# AudioInputs_16.net
KiCad netlist of a schematic drawn in Altium Designer
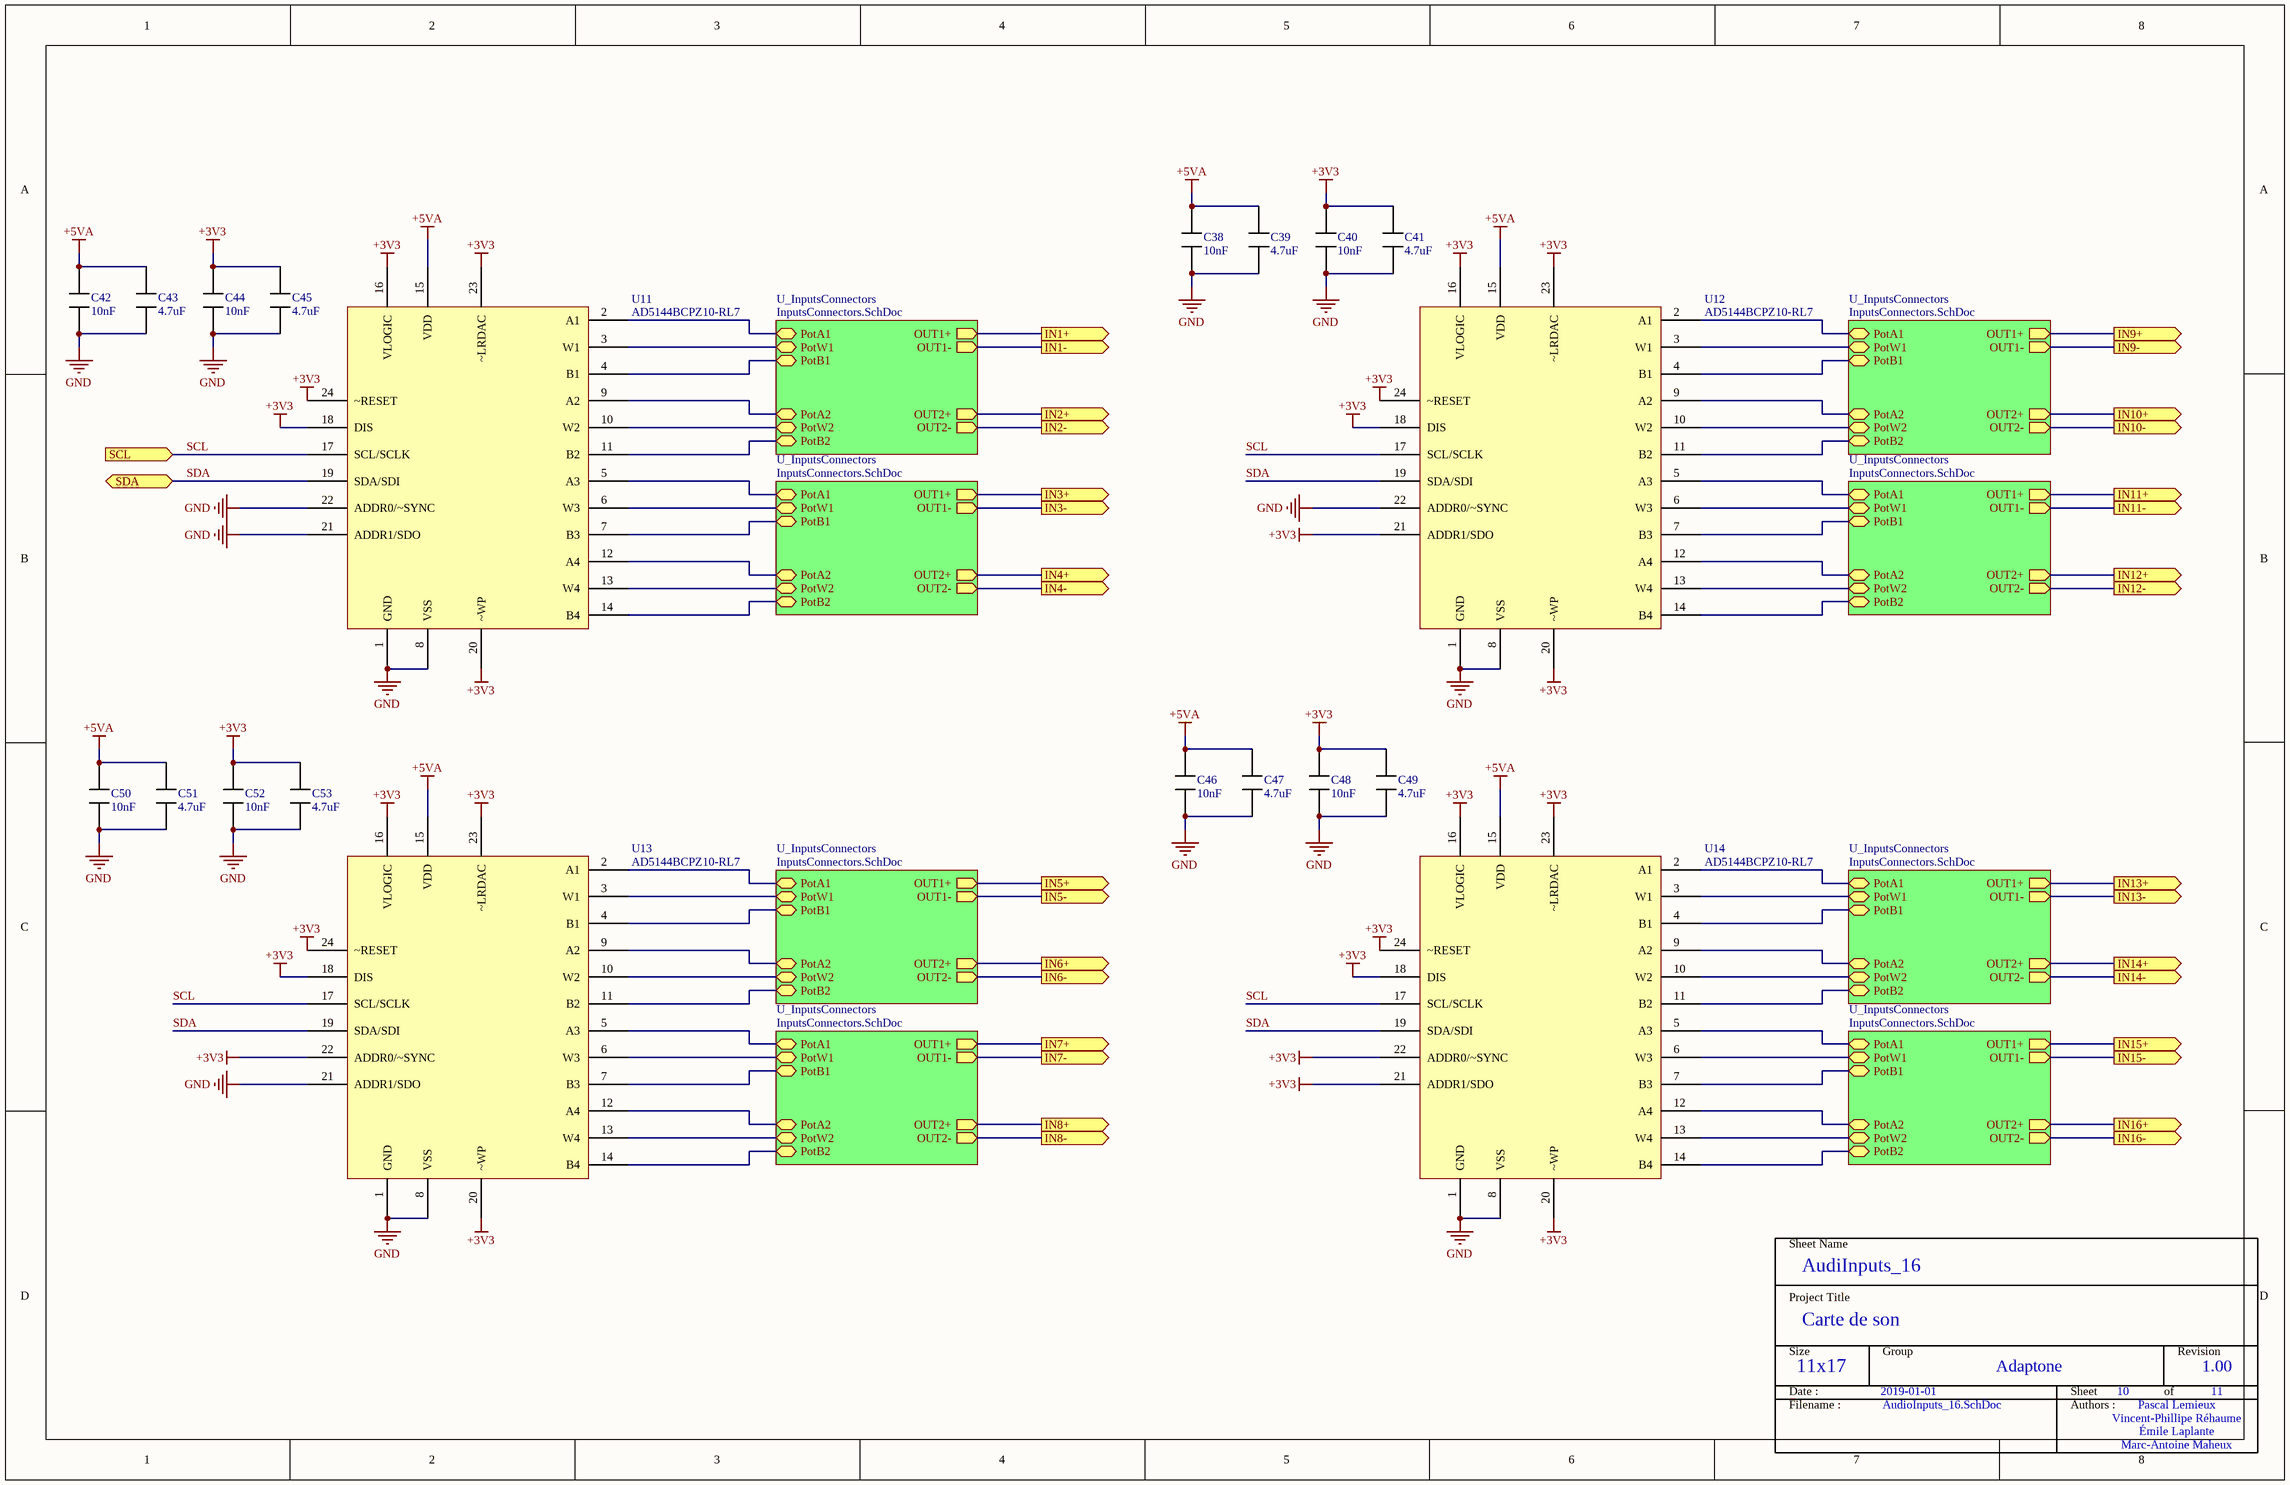
[diagram p0: AudioInputs_16.SchDoc]

(export (version "E")
  (design (tool "Eeschema 10.0.6"))
  (components
    (comp (ref "C38")
      (value "10nF")
      (footprint "0402")
      (description "Capacitor")
      (fields (field (name "MFG") "Samsung"))
      (libsource (lib "LIB_ADAPTONE_PASCAL_LEMIEUX") (part "Capacitor"))
    )
    (comp (ref "C39")
      (value "4.7uF")
      (footprint "0402")
      (description "Capacitor")
      (fields (field (name "MFG") "Samsung"))
      (libsource (lib "LIB_ADAPTONE_PASCAL_LEMIEUX") (part "Capacitor"))
    )
    (comp (ref "C40")
      (value "10nF")
      (footprint "0402")
      (description "Capacitor")
      (fields (field (name "MFG") "Samsung"))
      (libsource (lib "LIB_ADAPTONE_PASCAL_LEMIEUX") (part "Capacitor"))
    )
    (comp (ref "C41")
      (value "4.7uF")
      (footprint "0402")
      (description "Capacitor")
      (fields (field (name "MFG") "Samsung"))
      (libsource (lib "LIB_ADAPTONE_PASCAL_LEMIEUX") (part "Capacitor"))
    )
    (comp (ref "C42")
      (value "10nF")
      (footprint "0402")
      (description "Capacitor")
      (fields (field (name "MFG") "Samsung"))
      (libsource (lib "LIB_ADAPTONE_PASCAL_LEMIEUX") (part "Capacitor"))
    )
    (comp (ref "C43")
      (value "4.7uF")
      (footprint "0402")
      (description "Capacitor")
      (fields (field (name "MFG") "Samsung"))
      (libsource (lib "LIB_ADAPTONE_PASCAL_LEMIEUX") (part "Capacitor"))
    )
    (comp (ref "C44")
      (value "10nF")
      (footprint "0402")
      (description "Capacitor")
      (fields (field (name "MFG") "Samsung"))
      (libsource (lib "LIB_ADAPTONE_PASCAL_LEMIEUX") (part "Capacitor"))
    )
    (comp (ref "C45")
      (value "4.7uF")
      (footprint "0402")
      (description "Capacitor")
      (fields (field (name "MFG") "Samsung"))
      (libsource (lib "LIB_ADAPTONE_PASCAL_LEMIEUX") (part "Capacitor"))
    )
    (comp (ref "C46")
      (value "10nF")
      (footprint "0402")
      (description "Capacitor")
      (fields (field (name "MFG") "Samsung"))
      (libsource (lib "LIB_ADAPTONE_PASCAL_LEMIEUX") (part "Capacitor"))
    )
    (comp (ref "C47")
      (value "4.7uF")
      (footprint "0402")
      (description "Capacitor")
      (fields (field (name "MFG") "Samsung"))
      (libsource (lib "LIB_ADAPTONE_PASCAL_LEMIEUX") (part "Capacitor"))
    )
    (comp (ref "C48")
      (value "10nF")
      (footprint "0402")
      (description "Capacitor")
      (fields (field (name "MFG") "Samsung"))
      (libsource (lib "LIB_ADAPTONE_PASCAL_LEMIEUX") (part "Capacitor"))
    )
    (comp (ref "C49")
      (value "4.7uF")
      (footprint "0402")
      (description "Capacitor")
      (fields (field (name "MFG") "Samsung"))
      (libsource (lib "LIB_ADAPTONE_PASCAL_LEMIEUX") (part "Capacitor"))
    )
    (comp (ref "C50")
      (value "10nF")
      (footprint "0402")
      (description "Capacitor")
      (fields (field (name "MFG") "Samsung"))
      (libsource (lib "LIB_ADAPTONE_PASCAL_LEMIEUX") (part "Capacitor"))
    )
    (comp (ref "C51")
      (value "4.7uF")
      (footprint "0402")
      (description "Capacitor")
      (fields (field (name "MFG") "Samsung"))
      (libsource (lib "LIB_ADAPTONE_PASCAL_LEMIEUX") (part "Capacitor"))
    )
    (comp (ref "C52")
      (value "10nF")
      (footprint "0402")
      (description "Capacitor")
      (fields (field (name "MFG") "Samsung"))
      (libsource (lib "LIB_ADAPTONE_PASCAL_LEMIEUX") (part "Capacitor"))
    )
    (comp (ref "C53")
      (value "4.7uF")
      (footprint "0402")
      (description "Capacitor")
      (fields (field (name "MFG") "Samsung"))
      (libsource (lib "LIB_ADAPTONE_PASCAL_LEMIEUX") (part "Capacitor"))
    )
    (comp (ref "U11")
      (value "AD5144BCPZ10-RL7")
      (footprint "QFN50P400X400X100-25N")
      (fields (field (name "MFG") "Analog Devices Inc."))
      (libsource (lib "LIB_ADAPTONE_PASCAL_LEMIEUX") (part "AD5144BCPZ10-RL7"))
    )
    (comp (ref "U12")
      (value "AD5144BCPZ10-RL7")
      (footprint "QFN50P400X400X100-25N")
      (fields (field (name "MFG") "Analog Devices Inc."))
      (libsource (lib "LIB_ADAPTONE_PASCAL_LEMIEUX") (part "AD5144BCPZ10-RL7"))
    )
    (comp (ref "U13")
      (value "AD5144BCPZ10-RL7")
      (footprint "QFN50P400X400X100-25N")
      (fields (field (name "MFG") "Analog Devices Inc."))
      (libsource (lib "LIB_ADAPTONE_PASCAL_LEMIEUX") (part "AD5144BCPZ10-RL7"))
    )
    (comp (ref "U14")
      (value "AD5144BCPZ10-RL7")
      (footprint "QFN50P400X400X100-25N")
      (fields (field (name "MFG") "Analog Devices Inc."))
      (libsource (lib "LIB_ADAPTONE_PASCAL_LEMIEUX") (part "AD5144BCPZ10-RL7"))
    )
  )
  (nets
    (net (code "1") (name "+3V3") (class "Default")
      (node (ref "C40") (pin "1") (pintype "passive"))
      (node (ref "C41") (pin "1") (pintype "passive"))
      (node (ref "C44") (pin "1") (pintype "passive"))
      (node (ref "C45") (pin "1") (pintype "passive"))
      (node (ref "C48") (pin "1") (pintype "passive"))
      (node (ref "C49") (pin "1") (pintype "passive"))
      (node (ref "C52") (pin "1") (pintype "passive"))
      (node (ref "C53") (pin "1") (pintype "passive"))
      (node (ref "U11") (pin "16") (pinfunction "VLOGIC_16") (pintype "passive"))
      (node (ref "U11") (pin "18") (pinfunction "DIS_18") (pintype "passive"))
      (node (ref "U11") (pin "20") (pinfunction "~WP_20") (pintype "passive"))
      (node (ref "U11") (pin "23") (pinfunction "~LRDAC_23") (pintype "passive"))
      (node (ref "U11") (pin "24") (pinfunction "~RESET_24") (pintype "passive"))
      (node (ref "U12") (pin "16") (pinfunction "VLOGIC_16") (pintype "passive"))
      (node (ref "U12") (pin "18") (pinfunction "DIS_18") (pintype "passive"))
      (node (ref "U12") (pin "20") (pinfunction "~WP_20") (pintype "passive"))
      (node (ref "U12") (pin "21") (pinfunction "ADDR1/SDO_21") (pintype "passive"))
      (node (ref "U12") (pin "23") (pinfunction "~LRDAC_23") (pintype "passive"))
      (node (ref "U12") (pin "24") (pinfunction "~RESET_24") (pintype "passive"))
      (node (ref "U13") (pin "16") (pinfunction "VLOGIC_16") (pintype "passive"))
      (node (ref "U13") (pin "18") (pinfunction "DIS_18") (pintype "passive"))
      (node (ref "U13") (pin "20") (pinfunction "~WP_20") (pintype "passive"))
      (node (ref "U13") (pin "22") (pinfunction "ADDR0/~SYNC_22") (pintype "passive"))
      (node (ref "U13") (pin "23") (pinfunction "~LRDAC_23") (pintype "passive"))
      (node (ref "U13") (pin "24") (pinfunction "~RESET_24") (pintype "passive"))
      (node (ref "U14") (pin "16") (pinfunction "VLOGIC_16") (pintype "passive"))
      (node (ref "U14") (pin "18") (pinfunction "DIS_18") (pintype "passive"))
      (node (ref "U14") (pin "20") (pinfunction "~WP_20") (pintype "passive"))
      (node (ref "U14") (pin "21") (pinfunction "ADDR1/SDO_21") (pintype "passive"))
      (node (ref "U14") (pin "22") (pinfunction "ADDR0/~SYNC_22") (pintype "passive"))
      (node (ref "U14") (pin "23") (pinfunction "~LRDAC_23") (pintype "passive"))
      (node (ref "U14") (pin "24") (pinfunction "~RESET_24") (pintype "passive"))
    )
    (net (code "2") (name "+5VA") (class "Default")
      (node (ref "C38") (pin "1") (pintype "passive"))
      (node (ref "C39") (pin "1") (pintype "passive"))
      (node (ref "C42") (pin "1") (pintype "passive"))
      (node (ref "C43") (pin "1") (pintype "passive"))
      (node (ref "C46") (pin "1") (pintype "passive"))
      (node (ref "C47") (pin "1") (pintype "passive"))
      (node (ref "C50") (pin "1") (pintype "passive"))
      (node (ref "C51") (pin "1") (pintype "passive"))
      (node (ref "U11") (pin "15") (pinfunction "VDD_15") (pintype "passive"))
      (node (ref "U12") (pin "15") (pinfunction "VDD_15") (pintype "passive"))
      (node (ref "U13") (pin "15") (pinfunction "VDD_15") (pintype "passive"))
      (node (ref "U14") (pin "15") (pinfunction "VDD_15") (pintype "passive"))
    )
    (net (code "35") (name "/PotA1") (class "Default")
      (node (ref "U13") (pin "5") (pinfunction "A3_5") (pintype "passive"))
    )
    (net (code "36") (name "/PotA1_1") (class "Default")
      (node (ref "U14") (pin "5") (pinfunction "A3_5") (pintype "passive"))
    )
    (net (code "37") (name "/PotA1_2") (class "Default")
      (node (ref "U14") (pin "2") (pinfunction "A1_2") (pintype "passive"))
    )
    (net (code "38") (name "/PotA1_3") (class "Default")
      (node (ref "U12") (pin "2") (pinfunction "A1_2") (pintype "passive"))
    )
    (net (code "39") (name "/PotA1_4") (class "Default")
      (node (ref "U12") (pin "5") (pinfunction "A3_5") (pintype "passive"))
    )
    (net (code "40") (name "/PotA1_5") (class "Default")
      (node (ref "U11") (pin "5") (pinfunction "A3_5") (pintype "passive"))
    )
    (net (code "41") (name "/PotA1_6") (class "Default")
      (node (ref "U11") (pin "2") (pinfunction "A1_2") (pintype "passive"))
    )
    (net (code "42") (name "/PotA1_7") (class "Default")
      (node (ref "U13") (pin "2") (pinfunction "A1_2") (pintype "passive"))
    )
    (net (code "43") (name "/PotA2") (class "Default")
      (node (ref "U13") (pin "9") (pinfunction "A2_9") (pintype "passive"))
    )
    (net (code "44") (name "/PotA2_1") (class "Default")
      (node (ref "U14") (pin "12") (pinfunction "A4_12") (pintype "passive"))
    )
    (net (code "45") (name "/PotA2_2") (class "Default")
      (node (ref "U14") (pin "9") (pinfunction "A2_9") (pintype "passive"))
    )
    (net (code "46") (name "/PotA2_3") (class "Default")
      (node (ref "U12") (pin "9") (pinfunction "A2_9") (pintype "passive"))
    )
    (net (code "47") (name "/PotA2_4") (class "Default")
      (node (ref "U12") (pin "12") (pinfunction "A4_12") (pintype "passive"))
    )
    (net (code "48") (name "/PotA2_5") (class "Default")
      (node (ref "U11") (pin "9") (pinfunction "A2_9") (pintype "passive"))
    )
    (net (code "49") (name "/PotA2_6") (class "Default")
      (node (ref "U11") (pin "12") (pinfunction "A4_12") (pintype "passive"))
    )
    (net (code "50") (name "/PotA2_7") (class "Default")
      (node (ref "U13") (pin "12") (pinfunction "A4_12") (pintype "passive"))
    )
    (net (code "51") (name "/PotB1") (class "Default")
      (node (ref "U13") (pin "4") (pinfunction "B1_4") (pintype "passive"))
    )
    (net (code "52") (name "/PotB1_1") (class "Default")
      (node (ref "U14") (pin "7") (pinfunction "B3_7") (pintype "passive"))
    )
    (net (code "53") (name "/PotB1_2") (class "Default")
      (node (ref "U14") (pin "4") (pinfunction "B1_4") (pintype "passive"))
    )
    (net (code "54") (name "/PotB1_3") (class "Default")
      (node (ref "U12") (pin "4") (pinfunction "B1_4") (pintype "passive"))
    )
    (net (code "55") (name "/PotB1_4") (class "Default")
      (node (ref "U12") (pin "7") (pinfunction "B3_7") (pintype "passive"))
    )
    (net (code "56") (name "/PotB1_5") (class "Default")
      (node (ref "U11") (pin "4") (pinfunction "B1_4") (pintype "passive"))
    )
    (net (code "57") (name "/PotB1_6") (class "Default")
      (node (ref "U11") (pin "7") (pinfunction "B3_7") (pintype "passive"))
    )
    (net (code "58") (name "/PotB1_7") (class "Default")
      (node (ref "U13") (pin "7") (pinfunction "B3_7") (pintype "passive"))
    )
    (net (code "59") (name "/PotB2") (class "Default")
      (node (ref "U13") (pin "11") (pinfunction "B2_11") (pintype "passive"))
    )
    (net (code "60") (name "/PotB2_1") (class "Default")
      (node (ref "U14") (pin "14") (pinfunction "B4_14") (pintype "passive"))
    )
    (net (code "61") (name "/PotB2_2") (class "Default")
      (node (ref "U14") (pin "11") (pinfunction "B2_11") (pintype "passive"))
    )
    (net (code "62") (name "/PotB2_3") (class "Default")
      (node (ref "U12") (pin "11") (pinfunction "B2_11") (pintype "passive"))
    )
    (net (code "63") (name "/PotB2_4") (class "Default")
      (node (ref "U12") (pin "14") (pinfunction "B4_14") (pintype "passive"))
    )
    (net (code "64") (name "/PotB2_5") (class "Default")
      (node (ref "U11") (pin "11") (pinfunction "B2_11") (pintype "passive"))
    )
    (net (code "65") (name "/PotB2_6") (class "Default")
      (node (ref "U11") (pin "14") (pinfunction "B4_14") (pintype "passive"))
    )
    (net (code "66") (name "/PotB2_7") (class "Default")
      (node (ref "U13") (pin "14") (pinfunction "B4_14") (pintype "passive"))
    )
    (net (code "67") (name "/PotW1") (class "Default")
      (node (ref "U13") (pin "3") (pinfunction "W1_3") (pintype "passive"))
    )
    (net (code "68") (name "/PotW1_1") (class "Default")
      (node (ref "U14") (pin "6") (pinfunction "W3_6") (pintype "passive"))
    )
    (net (code "69") (name "/PotW1_2") (class "Default")
      (node (ref "U14") (pin "3") (pinfunction "W1_3") (pintype "passive"))
    )
    (net (code "70") (name "/PotW1_3") (class "Default")
      (node (ref "U12") (pin "3") (pinfunction "W1_3") (pintype "passive"))
    )
    (net (code "71") (name "/PotW1_4") (class "Default")
      (node (ref "U12") (pin "6") (pinfunction "W3_6") (pintype "passive"))
    )
    (net (code "72") (name "/PotW1_5") (class "Default")
      (node (ref "U11") (pin "6") (pinfunction "W3_6") (pintype "passive"))
    )
    (net (code "73") (name "/PotW1_6") (class "Default")
      (node (ref "U11") (pin "3") (pinfunction "W1_3") (pintype "passive"))
    )
    (net (code "74") (name "/PotW1_7") (class "Default")
      (node (ref "U13") (pin "6") (pinfunction "W3_6") (pintype "passive"))
    )
    (net (code "75") (name "/PotW2") (class "Default")
      (node (ref "U13") (pin "10") (pinfunction "W2_10") (pintype "passive"))
    )
    (net (code "76") (name "/PotW2_1") (class "Default")
      (node (ref "U14") (pin "13") (pinfunction "W4_13") (pintype "passive"))
    )
    (net (code "77") (name "/PotW2_2") (class "Default")
      (node (ref "U14") (pin "10") (pinfunction "W2_10") (pintype "passive"))
    )
    (net (code "78") (name "/PotW2_3") (class "Default")
      (node (ref "U12") (pin "10") (pinfunction "W2_10") (pintype "passive"))
    )
    (net (code "79") (name "/PotW2_4") (class "Default")
      (node (ref "U12") (pin "13") (pinfunction "W4_13") (pintype "passive"))
    )
    (net (code "80") (name "/PotW2_5") (class "Default")
      (node (ref "U11") (pin "10") (pinfunction "W2_10") (pintype "passive"))
    )
    (net (code "81") (name "/PotW2_6") (class "Default")
      (node (ref "U11") (pin "13") (pinfunction "W4_13") (pintype "passive"))
    )
    (net (code "82") (name "/PotW2_7") (class "Default")
      (node (ref "U13") (pin "13") (pinfunction "W4_13") (pintype "passive"))
    )
    (net (code "83") (name "/SCL") (class "Default")
      (node (ref "U11") (pin "17") (pinfunction "SCL/SCLK_17") (pintype "passive"))
      (node (ref "U12") (pin "17") (pinfunction "SCL/SCLK_17") (pintype "passive"))
      (node (ref "U13") (pin "17") (pinfunction "SCL/SCLK_17") (pintype "passive"))
      (node (ref "U14") (pin "17") (pinfunction "SCL/SCLK_17") (pintype "passive"))
    )
    (net (code "84") (name "/SDA") (class "Default")
      (node (ref "U11") (pin "19") (pinfunction "SDA/SDI_19") (pintype "passive"))
      (node (ref "U12") (pin "19") (pinfunction "SDA/SDI_19") (pintype "passive"))
      (node (ref "U13") (pin "19") (pinfunction "SDA/SDI_19") (pintype "passive"))
      (node (ref "U14") (pin "19") (pinfunction "SDA/SDI_19") (pintype "passive"))
    )
    (net (code "85") (name "GND") (class "Default")
      (node (ref "C38") (pin "2") (pintype "passive"))
      (node (ref "C39") (pin "2") (pintype "passive"))
      (node (ref "C40") (pin "2") (pintype "passive"))
      (node (ref "C41") (pin "2") (pintype "passive"))
      (node (ref "C42") (pin "2") (pintype "passive"))
      (node (ref "C43") (pin "2") (pintype "passive"))
      (node (ref "C44") (pin "2") (pintype "passive"))
      (node (ref "C45") (pin "2") (pintype "passive"))
      (node (ref "C46") (pin "2") (pintype "passive"))
      (node (ref "C47") (pin "2") (pintype "passive"))
      (node (ref "C48") (pin "2") (pintype "passive"))
      (node (ref "C49") (pin "2") (pintype "passive"))
      (node (ref "C50") (pin "2") (pintype "passive"))
      (node (ref "C51") (pin "2") (pintype "passive"))
      (node (ref "C52") (pin "2") (pintype "passive"))
      (node (ref "C53") (pin "2") (pintype "passive"))
      (node (ref "U11") (pin "1") (pinfunction "GND_1") (pintype "passive"))
      (node (ref "U11") (pin "21") (pinfunction "ADDR1/SDO_21") (pintype "passive"))
      (node (ref "U11") (pin "22") (pinfunction "ADDR0/~SYNC_22") (pintype "passive"))
      (node (ref "U11") (pin "8") (pinfunction "VSS_8") (pintype "passive"))
      (node (ref "U12") (pin "1") (pinfunction "GND_1") (pintype "passive"))
      (node (ref "U12") (pin "22") (pinfunction "ADDR0/~SYNC_22") (pintype "passive"))
      (node (ref "U12") (pin "8") (pinfunction "VSS_8") (pintype "passive"))
      (node (ref "U13") (pin "1") (pinfunction "GND_1") (pintype "passive"))
      (node (ref "U13") (pin "21") (pinfunction "ADDR1/SDO_21") (pintype "passive"))
      (node (ref "U13") (pin "8") (pinfunction "VSS_8") (pintype "passive"))
      (node (ref "U14") (pin "1") (pinfunction "GND_1") (pintype "passive"))
      (node (ref "U14") (pin "8") (pinfunction "VSS_8") (pintype "passive"))
    )
  )
)
